# PowerAdd.net
KiCad netlist of a schematic drawn in EAGLE
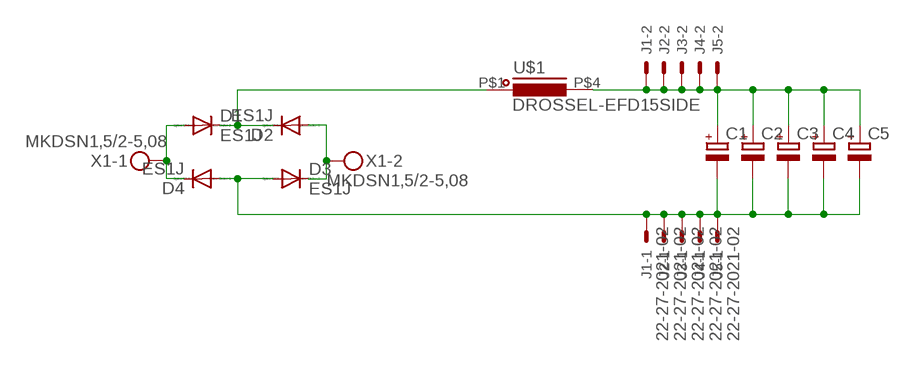
[diagram p0: schematic, sheet 1]

(export (version "E")
  (design (tool "Eeschema 10.0.6"))
  (components
    (comp (ref "C1")
      (value "CPOL-EUE2.5-6")
      (footprint "eagle-import:E2,5-6")
      (libsource (lib "eagle-import") (part "CPOL-EUE2.5-6"))
    )
    (comp (ref "C2")
      (value "CPOL-EUE2.5-6")
      (footprint "eagle-import:E2,5-6")
      (libsource (lib "eagle-import") (part "CPOL-EUE2.5-6"))
    )
    (comp (ref "C3")
      (value "CPOL-EUE2.5-6")
      (footprint "eagle-import:E2,5-6")
      (libsource (lib "eagle-import") (part "CPOL-EUE2.5-6"))
    )
    (comp (ref "C4")
      (value "CPOL-EUE2.5-6")
      (footprint "eagle-import:E2,5-6")
      (libsource (lib "eagle-import") (part "CPOL-EUE2.5-6"))
    )
    (comp (ref "C5")
      (value "CPOL-EUE2.5-6")
      (footprint "eagle-import:E2,5-6")
      (libsource (lib "eagle-import") (part "CPOL-EUE2.5-6"))
    )
    (comp (ref "D1")
      (value "ES1J")
      (footprint "eagle-import:DO214AC")
      (libsource (lib "eagle-import") (part "DIODE-DO214AC"))
    )
    (comp (ref "D2")
      (value "ES1J")
      (footprint "eagle-import:DO214AC")
      (libsource (lib "eagle-import") (part "DIODE-DO214AC"))
    )
    (comp (ref "D3")
      (value "ES1J")
      (footprint "eagle-import:DO214AC")
      (libsource (lib "eagle-import") (part "DIODE-DO214AC"))
    )
    (comp (ref "D4")
      (value "ES1J")
      (footprint "eagle-import:DO214AC")
      (libsource (lib "eagle-import") (part "DIODE-DO214AC"))
    )
    (comp (ref "J1")
      (value "22-27-2021-02")
      (footprint "eagle-import:6410-02")
      (libsource (lib "eagle-import") (part "22-?-0227-2021"))
    )
    (comp (ref "J2")
      (value "22-27-2021-02")
      (footprint "eagle-import:6410-02")
      (libsource (lib "eagle-import") (part "22-?-0227-2021"))
    )
    (comp (ref "J3")
      (value "22-27-2021-02")
      (footprint "eagle-import:6410-02")
      (libsource (lib "eagle-import") (part "22-?-0227-2021"))
    )
    (comp (ref "J4")
      (value "22-27-2021-02")
      (footprint "eagle-import:6410-02")
      (libsource (lib "eagle-import") (part "22-?-0227-2021"))
    )
    (comp (ref "J5")
      (value "22-27-2021-02")
      (footprint "eagle-import:6410-02")
      (libsource (lib "eagle-import") (part "22-?-0227-2021"))
    )
    (comp (ref "U$1")
      (value "DROSSEL-EFD15SIDE")
      (footprint "eagle-import:EFD15-4PIN")
      (libsource (lib "eagle-import") (part "DROSSEL-EFD15SIDE"))
    )
    (comp (ref "X1")
      (value "MKDSN1,5/2-5,08")
      (footprint "eagle-import:MKDSN1,5_2-5,08")
      (libsource (lib "eagle-import") (part "MKDSN1,5/2-5,08"))
    )
  )
  (nets
    (net (code "1") (name "Net-(J1A-S)") (class "Default")
      (node (ref "C1") (pin "-") (pinfunction "-_-") (pintype "passive"))
      (node (ref "C2") (pin "-") (pinfunction "-_-") (pintype "passive"))
      (node (ref "C3") (pin "-") (pinfunction "-_-") (pintype "passive"))
      (node (ref "C4") (pin "-") (pinfunction "-_-") (pintype "passive"))
      (node (ref "C5") (pin "-") (pinfunction "-_-") (pintype "passive"))
      (node (ref "D3") (pin "A") (pinfunction "A_A") (pintype "passive"))
      (node (ref "D4") (pin "A") (pinfunction "A_A") (pintype "passive"))
      (node (ref "J1") (pin "1") (pinfunction "S_1") (pintype "passive"))
      (node (ref "J2") (pin "1") (pinfunction "S_1") (pintype "passive"))
      (node (ref "J3") (pin "1") (pinfunction "S_1") (pintype "passive"))
      (node (ref "J4") (pin "1") (pinfunction "S_1") (pintype "passive"))
      (node (ref "J5") (pin "1") (pinfunction "S_1") (pintype "passive"))
    )
    (net (code "2") (name "Net-(J1B-S)") (class "Default")
      (node (ref "C1") (pin "+") (pinfunction "+_+") (pintype "passive"))
      (node (ref "C2") (pin "+") (pinfunction "+_+") (pintype "passive"))
      (node (ref "C3") (pin "+") (pinfunction "+_+") (pintype "passive"))
      (node (ref "C4") (pin "+") (pinfunction "+_+") (pintype "passive"))
      (node (ref "C5") (pin "+") (pinfunction "+_+") (pintype "passive"))
      (node (ref "J1") (pin "2") (pinfunction "S_2") (pintype "passive"))
      (node (ref "J2") (pin "2") (pinfunction "S_2") (pintype "passive"))
      (node (ref "J3") (pin "2") (pinfunction "S_2") (pintype "passive"))
      (node (ref "J4") (pin "2") (pinfunction "S_2") (pintype "passive"))
      (node (ref "J5") (pin "2") (pinfunction "S_2") (pintype "passive"))
      (node (ref "U$1") (pin "P$4") (pinfunction "2_P$4") (pintype "passive"))
    )
    (net (code "3") (name "Net-(U$1-1)") (class "Default")
      (node (ref "D1") (pin "C") (pinfunction "C_C") (pintype "passive"))
      (node (ref "D2") (pin "C") (pinfunction "C_C") (pintype "passive"))
      (node (ref "U$1") (pin "P$1") (pinfunction "1_P$1") (pintype "passive"))
    )
    (net (code "4") (name "Net-(X1A-KL)") (class "Default")
      (node (ref "D1") (pin "A") (pinfunction "A_A") (pintype "passive"))
      (node (ref "D4") (pin "C") (pinfunction "C_C") (pintype "passive"))
      (node (ref "X1") (pin "1") (pinfunction "KL_1") (pintype "passive"))
    )
    (net (code "5") (name "Net-(X1B-KL)") (class "Default")
      (node (ref "D2") (pin "A") (pinfunction "A_A") (pintype "passive"))
      (node (ref "D3") (pin "C") (pinfunction "C_C") (pintype "passive"))
      (node (ref "X1") (pin "2") (pinfunction "KL_2") (pintype "passive"))
    )
  )
)
